# Connecto-mcu.net
KiCad netlist of a schematic drawn in Altium Designer
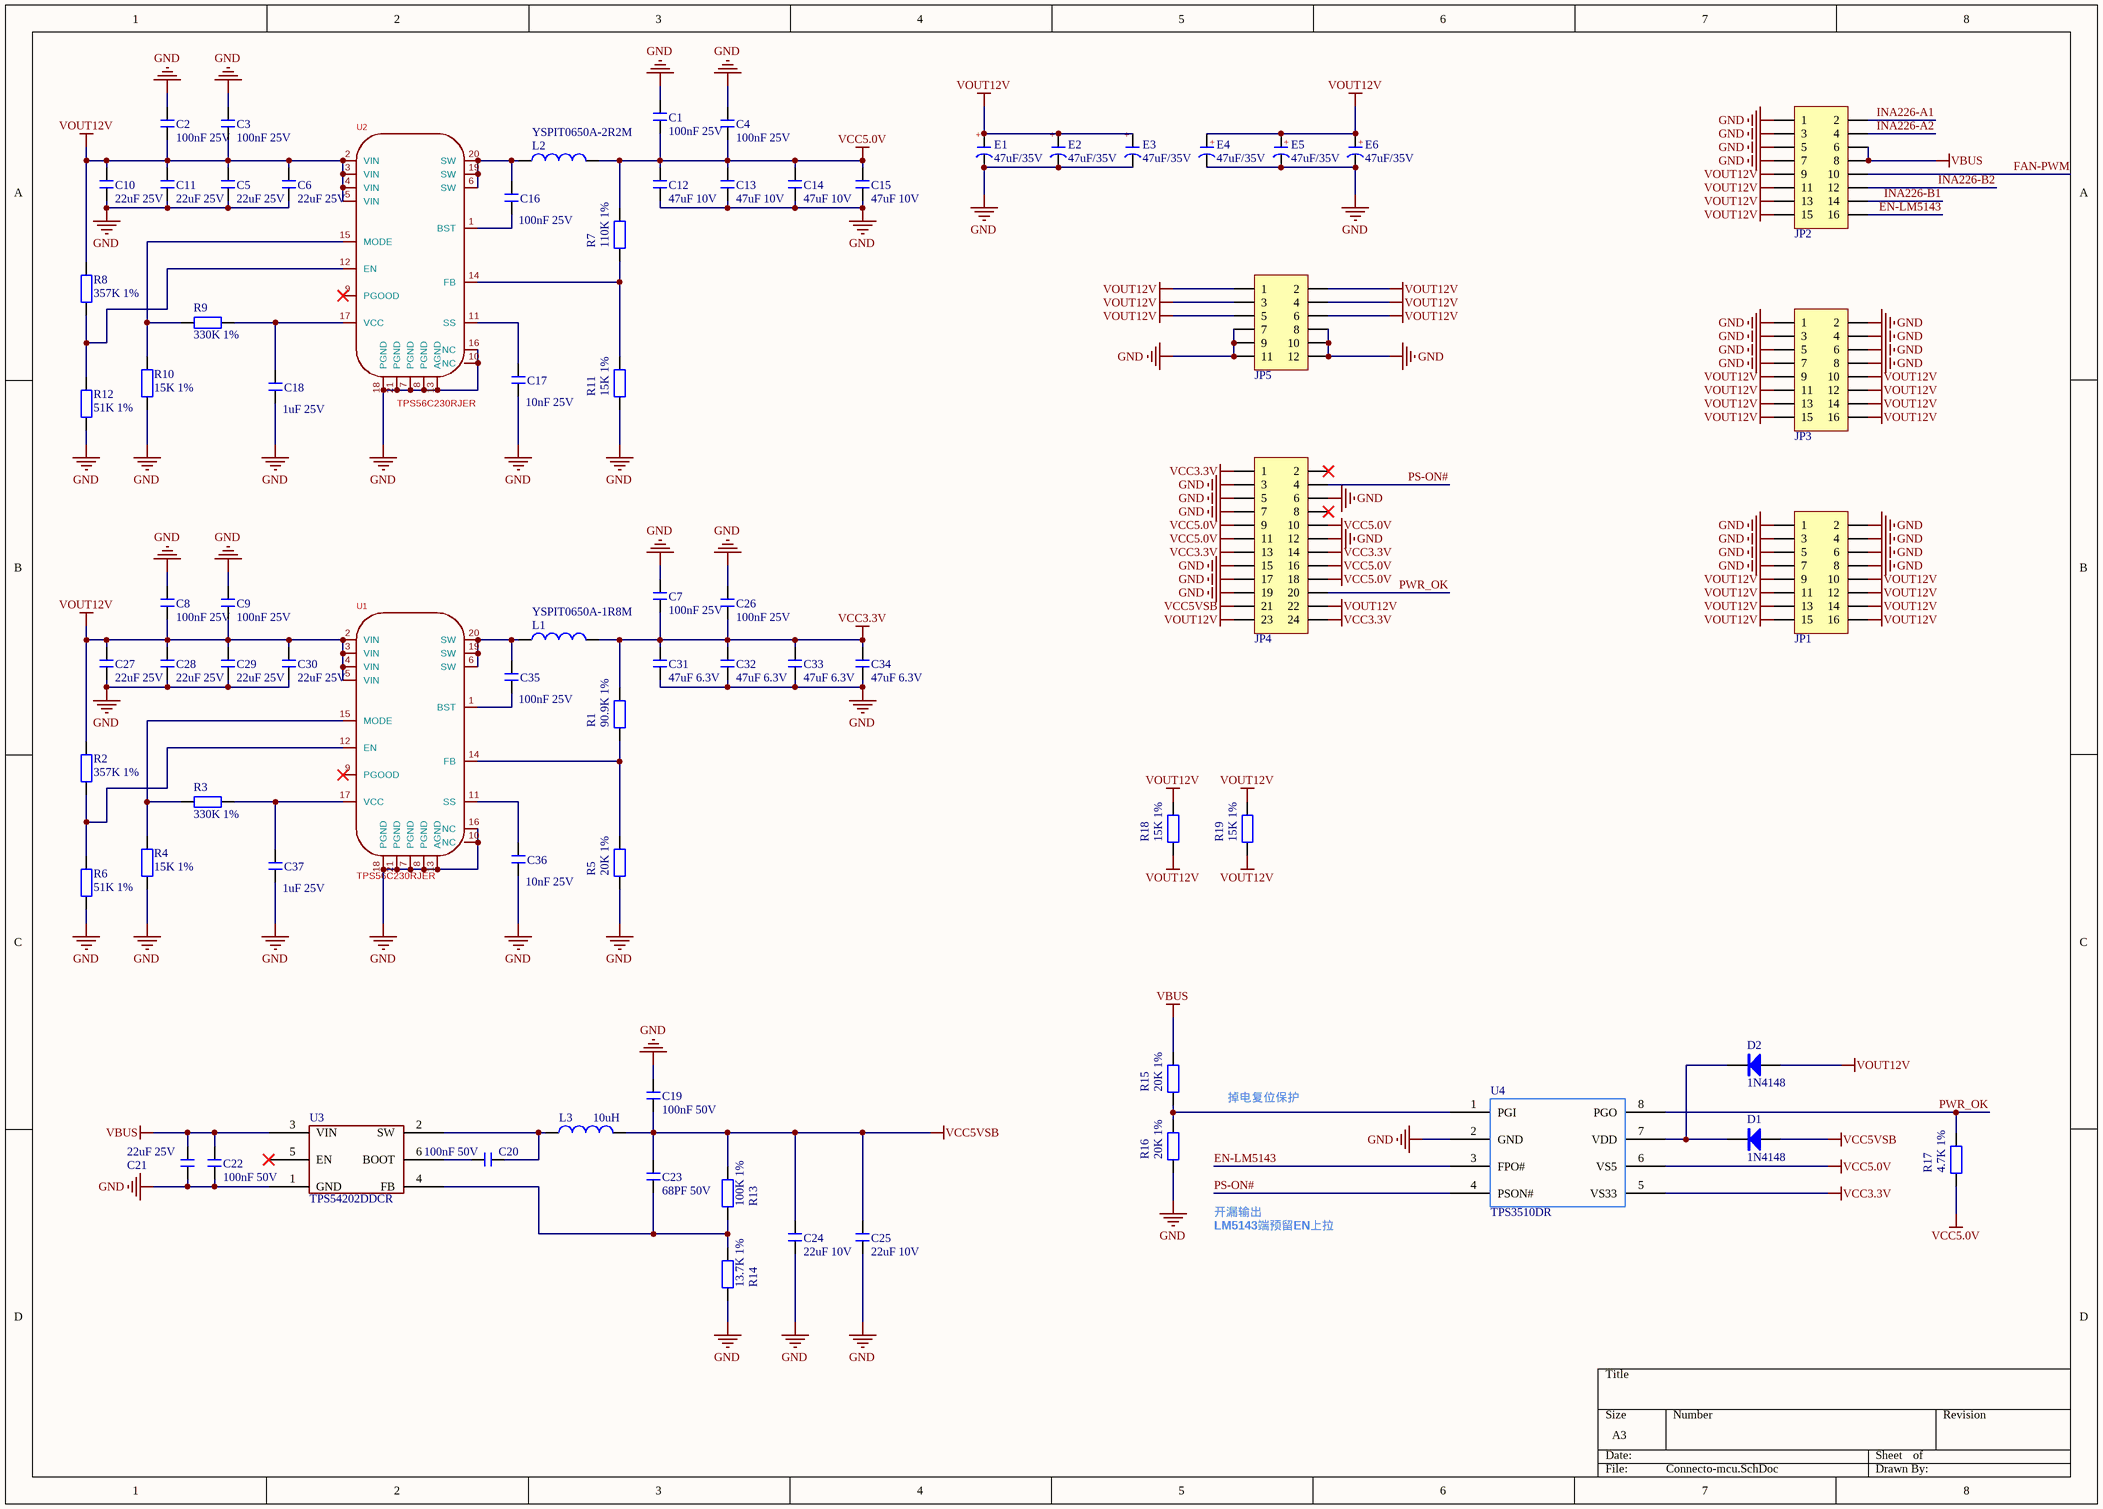
[diagram p0: Connecto-mcu.SchDoc]

(export (version "E")
  (design (tool "Eeschema 10.0.6"))
  (components
    (comp (ref "C1")
      (value "100nF 25V")
      (footprint "C0805_L")
      (description "无极性贴片电容")
      (fields (field (name "版权归属") "源创客"))
      (libsource (lib "Capacitor") (part "C"))
    )
    (comp (ref "C2")
      (value "100nF 25V")
      (footprint "C0402_L")
      (description "无极性贴片电容")
      (fields (field (name "版权归属") "源创客"))
      (libsource (lib "Capacitor") (part "C"))
    )
    (comp (ref "C3")
      (value "100nF 25V")
      (footprint "C0402_L")
      (description "无极性贴片电容")
      (fields (field (name "版权归属") "源创客"))
      (libsource (lib "Capacitor") (part "C"))
    )
    (comp (ref "C4")
      (value "100nF 25V")
      (footprint "C0805_L")
      (description "无极性贴片电容")
      (fields (field (name "版权归属") "源创客"))
      (libsource (lib "Capacitor") (part "C"))
    )
    (comp (ref "C5")
      (value "22uF 25V")
      (footprint "C0805_L")
      (description "无极性贴片电容")
      (fields (field (name "版权归属") "源创客"))
      (libsource (lib "Capacitor") (part "C"))
    )
    (comp (ref "C6")
      (value "22uF 25V")
      (footprint "C0805_L")
      (description "无极性贴片电容")
      (fields (field (name "版权归属") "源创客"))
      (libsource (lib "Capacitor") (part "C"))
    )
    (comp (ref "C7")
      (value "100nF 25V")
      (footprint "C0805_L")
      (description "无极性贴片电容")
      (fields (field (name "版权归属") "源创客"))
      (libsource (lib "Capacitor") (part "C"))
    )
    (comp (ref "C8")
      (value "100nF 25V")
      (footprint "C0402_L")
      (description "无极性贴片电容")
      (fields (field (name "版权归属") "源创客"))
      (libsource (lib "Capacitor") (part "C"))
    )
    (comp (ref "C9")
      (value "100nF 25V")
      (footprint "C0402_L")
      (description "无极性贴片电容")
      (fields (field (name "版权归属") "源创客"))
      (libsource (lib "Capacitor") (part "C"))
    )
    (comp (ref "C10")
      (value "22uF 25V")
      (footprint "C0805_L")
      (description "无极性贴片电容")
      (fields (field (name "版权归属") "源创客"))
      (libsource (lib "Capacitor") (part "C"))
    )
    (comp (ref "C11")
      (value "22uF 25V")
      (footprint "C0805_L")
      (description "无极性贴片电容")
      (fields (field (name "版权归属") "源创客"))
      (libsource (lib "Capacitor") (part "C"))
    )
    (comp (ref "C12")
      (value "47uF 10V")
      (footprint "C0805_L")
      (description "无极性贴片电容")
      (fields (field (name "版权归属") "源创客"))
      (libsource (lib "Capacitor") (part "C"))
    )
    (comp (ref "C13")
      (value "47uF 10V")
      (footprint "C0805_L")
      (description "无极性贴片电容")
      (fields (field (name "版权归属") "源创客"))
      (libsource (lib "Capacitor") (part "C"))
    )
    (comp (ref "C14")
      (value "47uF 10V")
      (footprint "C0805_L")
      (description "无极性贴片电容")
      (fields (field (name "版权归属") "源创客"))
      (libsource (lib "Capacitor") (part "C"))
    )
    (comp (ref "C15")
      (value "47uF 10V")
      (footprint "C0805_L")
      (description "无极性贴片电容")
      (fields (field (name "版权归属") "源创客"))
      (libsource (lib "Capacitor") (part "C"))
    )
    (comp (ref "C16")
      (value "100nF 25V")
      (footprint "C0402_L")
      (description "无极性贴片电容")
      (fields (field (name "版权归属") "源创客"))
      (libsource (lib "Capacitor") (part "C"))
    )
    (comp (ref "C17")
      (value "10nF 25V")
      (footprint "C0402_L")
      (description "无极性贴片电容")
      (fields (field (name "版权归属") "源创客"))
      (libsource (lib "Capacitor") (part "C"))
    )
    (comp (ref "C18")
      (value "1uF 25V")
      (footprint "C0402_L")
      (description "无极性贴片电容")
      (fields (field (name "版权归属") "源创客"))
      (libsource (lib "Capacitor") (part "C"))
    )
    (comp (ref "C19")
      (value "100nF 50V")
      (footprint "C0402_L")
      (description "无极性贴片电容")
      (fields (field (name "版权归属") "源创客"))
      (libsource (lib "Capacitor") (part "C"))
    )
    (comp (ref "C20")
      (value "100nF 50V")
      (footprint "C0402_L")
      (description "无极性贴片电容")
      (fields (field (name "版权归属") "源创客"))
      (libsource (lib "Capacitor") (part "C"))
    )
    (comp (ref "C21")
      (value "22uF 25V")
      (footprint "C0805_L")
      (description "无极性贴片电容")
      (fields (field (name "版权归属") "源创客"))
      (libsource (lib "Capacitor") (part "C"))
    )
    (comp (ref "C22")
      (value "100nF 50V")
      (footprint "C0402_L")
      (description "无极性贴片电容")
      (fields (field (name "版权归属") "源创客"))
      (libsource (lib "Capacitor") (part "C"))
    )
    (comp (ref "C23")
      (value "68PF 50V")
      (footprint "C0402_L")
      (description "无极性贴片电容")
      (fields (field (name "版权归属") "源创客"))
      (libsource (lib "Capacitor") (part "C"))
    )
    (comp (ref "C24")
      (value "22uF 10V")
      (footprint "C0805_L")
      (description "无极性贴片电容")
      (fields (field (name "版权归属") "源创客"))
      (libsource (lib "Capacitor") (part "C"))
    )
    (comp (ref "C25")
      (value "22uF 10V")
      (footprint "C0805_L")
      (description "无极性贴片电容")
      (fields (field (name "版权归属") "源创客"))
      (libsource (lib "Capacitor") (part "C"))
    )
    (comp (ref "C26")
      (value "100nF 25V")
      (footprint "C0805_L")
      (description "无极性贴片电容")
      (fields (field (name "版权归属") "源创客"))
      (libsource (lib "Capacitor") (part "C"))
    )
    (comp (ref "C27")
      (value "22uF 25V")
      (footprint "C0805_L")
      (description "无极性贴片电容")
      (fields (field (name "版权归属") "源创客"))
      (libsource (lib "Capacitor") (part "C"))
    )
    (comp (ref "C28")
      (value "22uF 25V")
      (footprint "C0805_L")
      (description "无极性贴片电容")
      (fields (field (name "版权归属") "源创客"))
      (libsource (lib "Capacitor") (part "C"))
    )
    (comp (ref "C29")
      (value "22uF 25V")
      (footprint "C0805_L")
      (description "无极性贴片电容")
      (fields (field (name "版权归属") "源创客"))
      (libsource (lib "Capacitor") (part "C"))
    )
    (comp (ref "C30")
      (value "22uF 25V")
      (footprint "C0805_L")
      (description "无极性贴片电容")
      (fields (field (name "版权归属") "源创客"))
      (libsource (lib "Capacitor") (part "C"))
    )
    (comp (ref "C31")
      (value "47uF 6.3V")
      (footprint "C0805_L")
      (description "无极性贴片电容")
      (fields (field (name "版权归属") "源创客"))
      (libsource (lib "Capacitor") (part "C"))
    )
    (comp (ref "C32")
      (value "47uF 6.3V")
      (footprint "C0805_L")
      (description "无极性贴片电容")
      (fields (field (name "版权归属") "源创客"))
      (libsource (lib "Capacitor") (part "C"))
    )
    (comp (ref "C33")
      (value "47uF 6.3V")
      (footprint "C0805_L")
      (description "无极性贴片电容")
      (fields (field (name "版权归属") "源创客"))
      (libsource (lib "Capacitor") (part "C"))
    )
    (comp (ref "C34")
      (value "47uF 6.3V")
      (footprint "C0805_L")
      (description "无极性贴片电容")
      (fields (field (name "版权归属") "源创客"))
      (libsource (lib "Capacitor") (part "C"))
    )
    (comp (ref "C35")
      (value "100nF 25V")
      (footprint "C0402_L")
      (description "无极性贴片电容")
      (fields (field (name "版权归属") "源创客"))
      (libsource (lib "Capacitor") (part "C"))
    )
    (comp (ref "C36")
      (value "10nF 25V")
      (footprint "C0402_L")
      (description "无极性贴片电容")
      (fields (field (name "版权归属") "源创客"))
      (libsource (lib "Capacitor") (part "C"))
    )
    (comp (ref "C37")
      (value "1uF 25V")
      (footprint "C0402_L")
      (description "无极性贴片电容")
      (fields (field (name "版权归属") "源创客"))
      (libsource (lib "Capacitor") (part "C"))
    )
    (comp (ref "D1")
      (value "1N4148")
      (footprint "SOD-523_L1.2-W0.8-LS1.6-FD")
      (description "整流二极管")
      (fields (field (name "版权归属") "源创客"))
      (libsource (lib "Diode") (part "1N4007"))
    )
    (comp (ref "D2")
      (value "1N4148")
      (footprint "SOD-523_L1.2-W0.8-LS1.6-FD")
      (description "整流二极管")
      (fields (field (name "版权归属") "源创客"))
      (libsource (lib "Diode") (part "1N4007"))
    )
    (comp (ref "E1")
      (value "47uF/35V")
      (footprint "CT 6*6 - V -A")
      (description "直插电解电容")
      (fields (field (name "版权归属") "源创客"))
      (libsource (lib "Capacitor") (part "C-CAP"))
    )
    (comp (ref "E2")
      (value "47uF/35V")
      (footprint "CT 6*6 - V -A")
      (description "直插电解电容")
      (fields (field (name "版权归属") "源创客"))
      (libsource (lib "Capacitor") (part "C-CAP"))
    )
    (comp (ref "E3")
      (value "47uF/35V")
      (footprint "CT 6*6 - V -A")
      (description "直插电解电容")
      (fields (field (name "版权归属") "源创客"))
      (libsource (lib "Capacitor") (part "C-CAP"))
    )
    (comp (ref "E4")
      (value "47uF/35V")
      (footprint "CT 6*6 - V -A")
      (description "直插电解电容")
      (fields (field (name "版权归属") "源创客"))
      (libsource (lib "") (part "C-CAP_1"))
    )
    (comp (ref "E5")
      (value "47uF/35V")
      (footprint "CT 6*6 - V -A")
      (description "直插电解电容")
      (fields (field (name "版权归属") "源创客"))
      (libsource (lib "") (part "C-CAP_1"))
    )
    (comp (ref "E6")
      (value "47uF/35V")
      (footprint "CT 6*6 - V -A")
      (description "直插电解电容")
      (fields (field (name "版权归属") "源创客"))
      (libsource (lib "") (part "C-CAP_1"))
    )
    (comp (ref "JP1")
      (value "Header 8X2")
      (footprint "HDR2.54-LI-2x8P")
      (description "8*2P接插件")
      (fields (field (name "版权归属") "源创客"))
      (libsource (lib "Connector-PinHeader") (part "Header 8X2"))
    )
    (comp (ref "JP2")
      (value "Header 8X2")
      (footprint "HDR2.54-LI-2x8P")
      (description "8*2P接插件")
      (fields (field (name "版权归属") "源创客"))
      (libsource (lib "Connector-PinHeader") (part "Header 8X2"))
    )
    (comp (ref "JP3")
      (value "Header 8X2")
      (footprint "HDR2.54-LI-2x8P")
      (description "8*2P接插件")
      (fields (field (name "版权归属") "源创客"))
      (libsource (lib "Connector-PinHeader") (part "Header 8X2"))
    )
    (comp (ref "JP4")
      (value "Header 2X11")
      (footprint "MX3.0 2X12 Pin 卧贴")
      (description "12*2P接插件")
      (fields (field (name "版权归属") "源创客"))
      (libsource (lib "Connector-PinHeader") (part "Header 12X2"))
    )
    (comp (ref "JP5")
      (value "Header 6X2")
      (footprint "MX3.0 2X6 Pin 卧贴")
      (description "6*2P接插件")
      (fields (field (name "版权归属") "源创客"))
      (libsource (lib "Connector-PinHeader") (part "Header  6X2"))
    )
    (comp (ref "L1")
      (value "YSPIT0650A-1R8M")
      (footprint "NR6045")
      (description "小功率贴片电感")
      (fields (field (name "版权归属") "源创客"))
      (libsource (lib "Inductor") (part "L"))
    )
    (comp (ref "L2")
      (value "YSPIT0650A-2R2M")
      (footprint "NR6045")
      (description "小功率贴片电感")
      (fields (field (name "版权归属") "源创客"))
      (libsource (lib "Inductor") (part "L"))
    )
    (comp (ref "L3")
      (value "10uH")
      (footprint "SMMS0420")
      (description "小功率贴片电感")
      (fields (field (name "版权归属") "源创客"))
      (libsource (lib "Inductor") (part "L"))
    )
    (comp (ref "R1")
      (value "90.9K 1%")
      (footprint "R0402_L")
      (description "贴片电阻")
      (fields (field (name "版权归属") "源创客"))
      (libsource (lib "Resistor") (part "R"))
    )
    (comp (ref "R2")
      (value "357K 1%")
      (footprint "R0402_L")
      (description "贴片电阻")
      (fields (field (name "版权归属") "源创客"))
      (libsource (lib "Resistor") (part "R"))
    )
    (comp (ref "R3")
      (value "330K 1%")
      (footprint "R0402_L")
      (description "贴片电阻")
      (fields (field (name "版权归属") "源创客"))
      (libsource (lib "Resistor") (part "R"))
    )
    (comp (ref "R4")
      (value "15K 1%")
      (footprint "R0402_L")
      (description "贴片电阻")
      (fields (field (name "版权归属") "源创客"))
      (libsource (lib "Resistor") (part "R"))
    )
    (comp (ref "R5")
      (value "20K 1%")
      (footprint "R0402_L")
      (description "贴片电阻")
      (fields (field (name "版权归属") "源创客"))
      (libsource (lib "Resistor") (part "R"))
    )
    (comp (ref "R6")
      (value "51K 1%")
      (footprint "R0402_L")
      (description "贴片电阻")
      (fields (field (name "版权归属") "源创客"))
      (libsource (lib "Resistor") (part "R"))
    )
    (comp (ref "R7")
      (value "110K 1%")
      (footprint "R0402_L")
      (description "贴片电阻")
      (fields (field (name "版权归属") "源创客"))
      (libsource (lib "Resistor") (part "R"))
    )
    (comp (ref "R8")
      (value "357K 1%")
      (footprint "R0402_L")
      (description "贴片电阻")
      (fields (field (name "版权归属") "源创客"))
      (libsource (lib "Resistor") (part "R"))
    )
    (comp (ref "R9")
      (value "330K 1%")
      (footprint "R0402_L")
      (description "贴片电阻")
      (fields (field (name "版权归属") "源创客"))
      (libsource (lib "Resistor") (part "R"))
    )
    (comp (ref "R10")
      (value "15K 1%")
      (footprint "R0402_L")
      (description "贴片电阻")
      (fields (field (name "版权归属") "源创客"))
      (libsource (lib "Resistor") (part "R"))
    )
    (comp (ref "R11")
      (value "15K 1%")
      (footprint "R0402_L")
      (description "贴片电阻")
      (fields (field (name "版权归属") "源创客"))
      (libsource (lib "Resistor") (part "R"))
    )
    (comp (ref "R12")
      (value "51K 1%")
      (footprint "R0402_L")
      (description "贴片电阻")
      (fields (field (name "版权归属") "源创客"))
      (libsource (lib "Resistor") (part "R"))
    )
    (comp (ref "R13")
      (value "100K 1%")
      (footprint "R0402_L")
      (description "贴片电阻")
      (fields (field (name "版权归属") "源创客"))
      (libsource (lib "Resistor") (part "R"))
    )
    (comp (ref "R14")
      (value "13.7K 1%")
      (footprint "R0402_L")
      (description "贴片电阻")
      (fields (field (name "版权归属") "源创客"))
      (libsource (lib "Resistor") (part "R"))
    )
    (comp (ref "R15")
      (value "20K 1%")
      (footprint "R0402_L")
      (description "贴片电阻")
      (fields (field (name "版权归属") "源创客"))
      (libsource (lib "Resistor") (part "R"))
    )
    (comp (ref "R16")
      (value "20K 1%")
      (footprint "R0402_L")
      (description "贴片电阻")
      (fields (field (name "版权归属") "源创客"))
      (libsource (lib "Resistor") (part "R"))
    )
    (comp (ref "R17")
      (value "4.7K 1%")
      (footprint "R0402_L")
      (description "贴片电阻")
      (fields (field (name "版权归属") "源创客"))
      (libsource (lib "Resistor") (part "R"))
    )
    (comp (ref "R18")
      (value "15K 1%")
      (footprint "内嵌载流铜条 2x2x66.5mm")
      (description "贴片电阻")
      (fields (field (name "版权归属") "源创客"))
      (libsource (lib "Resistor") (part "R"))
    )
    (comp (ref "R19")
      (value "15K 1%")
      (footprint "内嵌载流铜条 2x2x66.5mm")
      (description "贴片电阻")
      (fields (field (name "版权归属") "源创客"))
      (libsource (lib "Resistor") (part "R"))
    )
    (comp (ref "U1")
      (value "TPS56C230RJER")
      (footprint "VQFN-20_L3.0-W3.0-P0.45-TL-EP_TI_RJE")
      (description "功能类型:降压型;输出类型:可调;输入电压:4.5V~18V;输出电压:600mV~5.5V;输出电流(最大值):12A;")
      (fields (field (name "MANUFACTURER") "TI(德州仪器)"))
      (libsource (lib "DCDC Convert") (part "TPS56C230RJER"))
    )
    (comp (ref "U2")
      (value "TPS56C230RJER")
      (footprint "VQFN-20_L3.0-W3.0-P0.45-TL-EP_TI_RJE")
      (description "功能类型:降压型;输出类型:可调;输入电压:4.5V~18V;输出电压:600mV~5.5V;输出电流(最大值):12A;")
      (fields (field (name "MANUFACTURER") "TI(德州仪器)"))
      (libsource (lib "DCDC Convert") (part "TPS56C230RJER"))
    )
    (comp (ref "U3")
      (value "TPS54202DDCR")
      (footprint "SOT23-6L")
      (description "DCDC Convert")
      (libsource (lib "DCDC Convert") (part "TPS54202DDCR"))
    )
    (comp (ref "U4")
      (value "TPS3510DR")
      (footprint "SOP8_N")
      (description "TPS3510 适用于开关模式电源的 3 通道监控器")
      (libsource (lib "监控和复位芯片") (part "TPS3510DR"))
    )
  )
  (nets
    (net (code "1") (name "/EN-LM5143") (class "Default")
      (node (ref "JP2") (pin "16") (pinfunction "16_16") (pintype "passive"))
      (node (ref "U4") (pin "3") (pinfunction "FPO#_3") (pintype "passive"))
    )
    (net (code "2") (name "/FAN-PWM") (class "Default")
      (node (ref "JP2") (pin "10") (pinfunction "10_10") (pintype "passive"))
    )
    (net (code "3") (name "/INA226-A1") (class "Default")
      (node (ref "JP2") (pin "2") (pinfunction "2_2") (pintype "passive"))
    )
    (net (code "4") (name "/INA226-A2") (class "Default")
      (node (ref "JP2") (pin "4") (pinfunction "4_4") (pintype "passive"))
    )
    (net (code "5") (name "/INA226-B1") (class "Default")
      (node (ref "JP2") (pin "14") (pinfunction "14_14") (pintype "passive"))
    )
    (net (code "6") (name "/INA226-B2") (class "Default")
      (node (ref "JP2") (pin "12") (pinfunction "12_12") (pintype "passive"))
    )
    (net (code "7") (name "/PS-ON#") (class "Default")
      (node (ref "JP4") (pin "4") (pinfunction "4_4") (pintype "passive"))
      (node (ref "U4") (pin "4") (pinfunction "PSON#_4") (pintype "passive"))
    )
    (net (code "8") (name "/PWR_OK") (class "Default")
      (node (ref "JP4") (pin "20") (pinfunction "20_20") (pintype "passive"))
      (node (ref "R17") (pin "1") (pinfunction "1_1") (pintype "passive"))
      (node (ref "U4") (pin "8") (pinfunction "PGO_8") (pintype "passive"))
    )
    (net (code "9") (name "GND") (class "Default")
      (node (ref "C1") (pin "2") (pinfunction "2_2") (pintype "passive"))
      (node (ref "C10") (pin "1") (pinfunction "1_1") (pintype "passive"))
      (node (ref "C11") (pin "1") (pinfunction "1_1") (pintype "passive"))
      (node (ref "C12") (pin "1") (pinfunction "1_1") (pintype "passive"))
      (node (ref "C13") (pin "1") (pinfunction "1_1") (pintype "passive"))
      (node (ref "C14") (pin "1") (pinfunction "1_1") (pintype "passive"))
      (node (ref "C15") (pin "1") (pinfunction "1_1") (pintype "passive"))
      (node (ref "C17") (pin "1") (pinfunction "1_1") (pintype "passive"))
      (node (ref "C18") (pin "1") (pinfunction "1_1") (pintype "passive"))
      (node (ref "C19") (pin "2") (pinfunction "2_2") (pintype "passive"))
      (node (ref "C2") (pin "2") (pinfunction "2_2") (pintype "passive"))
      (node (ref "C21") (pin "1") (pinfunction "1_1") (pintype "passive"))
      (node (ref "C22") (pin "1") (pinfunction "1_1") (pintype "passive"))
      (node (ref "C24") (pin "2") (pinfunction "2_2") (pintype "passive"))
      (node (ref "C25") (pin "2") (pinfunction "2_2") (pintype "passive"))
      (node (ref "C26") (pin "2") (pinfunction "2_2") (pintype "passive"))
      (node (ref "C27") (pin "1") (pinfunction "1_1") (pintype "passive"))
      (node (ref "C28") (pin "1") (pinfunction "1_1") (pintype "passive"))
      (node (ref "C29") (pin "1") (pinfunction "1_1") (pintype "passive"))
      (node (ref "C3") (pin "2") (pinfunction "2_2") (pintype "passive"))
      (node (ref "C30") (pin "1") (pinfunction "1_1") (pintype "passive"))
      (node (ref "C31") (pin "1") (pinfunction "1_1") (pintype "passive"))
      (node (ref "C32") (pin "1") (pinfunction "1_1") (pintype "passive"))
      (node (ref "C33") (pin "1") (pinfunction "1_1") (pintype "passive"))
      (node (ref "C34") (pin "1") (pinfunction "1_1") (pintype "passive"))
      (node (ref "C36") (pin "1") (pinfunction "1_1") (pintype "passive"))
      (node (ref "C37") (pin "1") (pinfunction "1_1") (pintype "passive"))
      (node (ref "C4") (pin "2") (pinfunction "2_2") (pintype "passive"))
      (node (ref "C5") (pin "1") (pinfunction "1_1") (pintype "passive"))
      (node (ref "C6") (pin "1") (pinfunction "1_1") (pintype "passive"))
      (node (ref "C7") (pin "2") (pinfunction "2_2") (pintype "passive"))
      (node (ref "C8") (pin "2") (pinfunction "2_2") (pintype "passive"))
      (node (ref "C9") (pin "2") (pinfunction "2_2") (pintype "passive"))
      (node (ref "E1") (pin "2") (pinfunction "K_2") (pintype "passive"))
      (node (ref "E2") (pin "2") (pinfunction "K_2") (pintype "passive"))
      (node (ref "E3") (pin "2") (pinfunction "K_2") (pintype "passive"))
      (node (ref "E4") (pin "2") (pinfunction "K_2") (pintype "passive"))
      (node (ref "E5") (pin "2") (pinfunction "K_2") (pintype "passive"))
      (node (ref "E6") (pin "2") (pinfunction "K_2") (pintype "passive"))
      (node (ref "JP1") (pin "1") (pinfunction "1_1") (pintype "passive"))
      (node (ref "JP1") (pin "2") (pinfunction "2_2") (pintype "passive"))
      (node (ref "JP1") (pin "3") (pinfunction "3_3") (pintype "passive"))
      (node (ref "JP1") (pin "4") (pinfunction "4_4") (pintype "passive"))
      (node (ref "JP1") (pin "5") (pinfunction "5_5") (pintype "passive"))
      (node (ref "JP1") (pin "6") (pinfunction "6_6") (pintype "passive"))
      (node (ref "JP1") (pin "7") (pinfunction "7_7") (pintype "passive"))
      (node (ref "JP1") (pin "8") (pinfunction "8_8") (pintype "passive"))
      (node (ref "JP2") (pin "1") (pinfunction "1_1") (pintype "passive"))
      (node (ref "JP2") (pin "3") (pinfunction "3_3") (pintype "passive"))
      (node (ref "JP2") (pin "5") (pinfunction "5_5") (pintype "passive"))
      (node (ref "JP2") (pin "7") (pinfunction "7_7") (pintype "passive"))
      (node (ref "JP3") (pin "1") (pinfunction "1_1") (pintype "passive"))
      (node (ref "JP3") (pin "2") (pinfunction "2_2") (pintype "passive"))
      (node (ref "JP3") (pin "3") (pinfunction "3_3") (pintype "passive"))
      (node (ref "JP3") (pin "4") (pinfunction "4_4") (pintype "passive"))
      (node (ref "JP3") (pin "5") (pinfunction "5_5") (pintype "passive"))
      (node (ref "JP3") (pin "6") (pinfunction "6_6") (pintype "passive"))
      (node (ref "JP3") (pin "7") (pinfunction "7_7") (pintype "passive"))
      (node (ref "JP3") (pin "8") (pinfunction "8_8") (pintype "passive"))
      (node (ref "JP4") (pin "12") (pinfunction "12_12") (pintype "passive"))
      (node (ref "JP4") (pin "15") (pinfunction "15_15") (pintype "passive"))
      (node (ref "JP4") (pin "17") (pinfunction "17_17") (pintype "passive"))
      (node (ref "JP4") (pin "19") (pinfunction "19_19") (pintype "passive"))
      (node (ref "JP4") (pin "3") (pinfunction "3_3") (pintype "passive"))
      (node (ref "JP4") (pin "5") (pinfunction "5_5") (pintype "passive"))
      (node (ref "JP4") (pin "6") (pinfunction "6_6") (pintype "passive"))
      (node (ref "JP4") (pin "7") (pinfunction "7_7") (pintype "passive"))
      (node (ref "JP5") (pin "10") (pinfunction "10_10") (pintype "passive"))
      (node (ref "JP5") (pin "11") (pinfunction "11_11") (pintype "passive"))
      (node (ref "JP5") (pin "12") (pinfunction "12_12") (pintype "passive"))
      (node (ref "JP5") (pin "7") (pinfunction "7_7") (pintype "passive"))
      (node (ref "JP5") (pin "8") (pinfunction "8_8") (pintype "passive"))
      (node (ref "JP5") (pin "9") (pinfunction "9_9") (pintype "passive"))
      (node (ref "R10") (pin "1") (pinfunction "1_1") (pintype "passive"))
      (node (ref "R11") (pin "2") (pinfunction "2_2") (pintype "passive"))
      (node (ref "R12") (pin "1") (pinfunction "1_1") (pintype "passive"))
      (node (ref "R14") (pin "2") (pinfunction "2_2") (pintype "passive"))
      (node (ref "R16") (pin "2") (pinfunction "2_2") (pintype "passive"))
      (node (ref "R4") (pin "1") (pinfunction "1_1") (pintype "passive"))
      (node (ref "R5") (pin "2") (pinfunction "2_2") (pintype "passive"))
      (node (ref "R6") (pin "1") (pinfunction "1_1") (pintype "passive"))
      (node (ref "U1") (pin "10") (pinfunction "NC_10") (pintype "passive"))
      (node (ref "U1") (pin "13") (pinfunction "AGND_13") (pintype "passive"))
      (node (ref "U1") (pin "16") (pinfunction "NC_16") (pintype "passive"))
      (node (ref "U1") (pin "18") (pinfunction "PGND_18") (pintype "passive"))
      (node (ref "U1") (pin "21") (pinfunction "PGND_21") (pintype "passive"))
      (node (ref "U1") (pin "7") (pinfunction "PGND_7") (pintype "passive"))
      (node (ref "U1") (pin "8") (pinfunction "PGND_8") (pintype "passive"))
      (node (ref "U2") (pin "10") (pinfunction "NC_10") (pintype "passive"))
      (node (ref "U2") (pin "13") (pinfunction "AGND_13") (pintype "passive"))
      (node (ref "U2") (pin "16") (pinfunction "NC_16") (pintype "passive"))
      (node (ref "U2") (pin "18") (pinfunction "PGND_18") (pintype "passive"))
      (node (ref "U2") (pin "21") (pinfunction "PGND_21") (pintype "passive"))
      (node (ref "U2") (pin "7") (pinfunction "PGND_7") (pintype "passive"))
      (node (ref "U2") (pin "8") (pinfunction "PGND_8") (pintype "passive"))
      (node (ref "U3") (pin "1") (pinfunction "GND_1") (pintype "passive"))
      (node (ref "U4") (pin "2") (pinfunction "GND_2") (pintype "passive"))
    )
    (net (code "10") (name "Net-(C16-Pad2)") (class "Default")
      (node (ref "C16") (pin "2") (pinfunction "2_2") (pintype "passive"))
      (node (ref "L2") (pin "1") (pinfunction "1_1") (pintype "passive"))
      (node (ref "U2") (pin "19") (pinfunction "SW_19") (pintype "passive"))
      (node (ref "U2") (pin "20") (pinfunction "SW_20") (pintype "passive"))
      (node (ref "U2") (pin "6") (pinfunction "SW_6") (pintype "passive"))
    )
    (net (code "11") (name "Net-(C35-Pad2)") (class "Default")
      (node (ref "C35") (pin "2") (pinfunction "2_2") (pintype "passive"))
      (node (ref "L1") (pin "1") (pinfunction "1_1") (pintype "passive"))
      (node (ref "U1") (pin "19") (pinfunction "SW_19") (pintype "passive"))
      (node (ref "U1") (pin "20") (pinfunction "SW_20") (pintype "passive"))
      (node (ref "U1") (pin "6") (pinfunction "SW_6") (pintype "passive"))
    )
    (net (code "12") (name "Net-(D1-K)") (class "Default")
      (node (ref "D1") (pin "2") (pinfunction "K_2") (pintype "passive"))
      (node (ref "D2") (pin "2") (pinfunction "K_2") (pintype "passive"))
      (node (ref "U4") (pin "7") (pinfunction "VDD_7") (pintype "passive"))
    )
    (net (code "13") (name "Net-(U1-BST)") (class "Default")
      (node (ref "C35") (pin "1") (pinfunction "1_1") (pintype "passive"))
      (node (ref "U1") (pin "1") (pinfunction "BST_1") (pintype "passive"))
    )
    (net (code "14") (name "Net-(U1-EN)") (class "Default")
      (node (ref "R2") (pin "1") (pinfunction "1_1") (pintype "passive"))
      (node (ref "R6") (pin "2") (pinfunction "2_2") (pintype "passive"))
      (node (ref "U1") (pin "12") (pinfunction "EN_12") (pintype "passive"))
    )
    (net (code "15") (name "Net-(U1-FB)") (class "Default")
      (node (ref "R1") (pin "2") (pinfunction "2_2") (pintype "passive"))
      (node (ref "R5") (pin "1") (pinfunction "1_1") (pintype "passive"))
      (node (ref "U1") (pin "14") (pinfunction "FB_14") (pintype "passive"))
    )
    (net (code "16") (name "Net-(U1-MODE)") (class "Default")
      (node (ref "R3") (pin "2") (pinfunction "2_2") (pintype "passive"))
      (node (ref "R4") (pin "2") (pinfunction "2_2") (pintype "passive"))
      (node (ref "U1") (pin "15") (pinfunction "MODE_15") (pintype "passive"))
    )
    (net (code "17") (name "Net-(U1-SS)") (class "Default")
      (node (ref "C36") (pin "2") (pinfunction "2_2") (pintype "passive"))
      (node (ref "U1") (pin "11") (pinfunction "SS_11") (pintype "passive"))
    )
    (net (code "18") (name "Net-(U1-VCC)") (class "Default")
      (node (ref "C37") (pin "2") (pinfunction "2_2") (pintype "passive"))
      (node (ref "R3") (pin "1") (pinfunction "1_1") (pintype "passive"))
      (node (ref "U1") (pin "17") (pinfunction "VCC_17") (pintype "passive"))
    )
    (net (code "19") (name "Net-(U2-BST)") (class "Default")
      (node (ref "C16") (pin "1") (pinfunction "1_1") (pintype "passive"))
      (node (ref "U2") (pin "1") (pinfunction "BST_1") (pintype "passive"))
    )
    (net (code "20") (name "Net-(U2-EN)") (class "Default")
      (node (ref "R12") (pin "2") (pinfunction "2_2") (pintype "passive"))
      (node (ref "R8") (pin "1") (pinfunction "1_1") (pintype "passive"))
      (node (ref "U2") (pin "12") (pinfunction "EN_12") (pintype "passive"))
    )
    (net (code "21") (name "Net-(U2-FB)") (class "Default")
      (node (ref "R11") (pin "1") (pinfunction "1_1") (pintype "passive"))
      (node (ref "R7") (pin "2") (pinfunction "2_2") (pintype "passive"))
      (node (ref "U2") (pin "14") (pinfunction "FB_14") (pintype "passive"))
    )
    (net (code "22") (name "Net-(U2-MODE)") (class "Default")
      (node (ref "R10") (pin "2") (pinfunction "2_2") (pintype "passive"))
      (node (ref "R9") (pin "2") (pinfunction "2_2") (pintype "passive"))
      (node (ref "U2") (pin "15") (pinfunction "MODE_15") (pintype "passive"))
    )
    (net (code "23") (name "Net-(U2-SS)") (class "Default")
      (node (ref "C17") (pin "2") (pinfunction "2_2") (pintype "passive"))
      (node (ref "U2") (pin "11") (pinfunction "SS_11") (pintype "passive"))
    )
    (net (code "24") (name "Net-(U2-VCC)") (class "Default")
      (node (ref "C18") (pin "2") (pinfunction "2_2") (pintype "passive"))
      (node (ref "R9") (pin "1") (pinfunction "1_1") (pintype "passive"))
      (node (ref "U2") (pin "17") (pinfunction "VCC_17") (pintype "passive"))
    )
    (net (code "25") (name "Net-(U3-BOOT)") (class "Default")
      (node (ref "C20") (pin "1") (pinfunction "1_1") (pintype "passive"))
      (node (ref "U3") (pin "6") (pinfunction "BOOT_6") (pintype "passive"))
    )
    (net (code "26") (name "Net-(U3-FB)") (class "Default")
      (node (ref "C23") (pin "1") (pinfunction "1_1") (pintype "passive"))
      (node (ref "R13") (pin "2") (pinfunction "2_2") (pintype "passive"))
      (node (ref "R14") (pin "1") (pinfunction "1_1") (pintype "passive"))
      (node (ref "U3") (pin "4") (pinfunction "FB_4") (pintype "passive"))
    )
    (net (code "27") (name "Net-(U3-SW)") (class "Default")
      (node (ref "C20") (pin "2") (pinfunction "2_2") (pintype "passive"))
      (node (ref "L3") (pin "1") (pinfunction "1_1") (pintype "passive"))
      (node (ref "U3") (pin "2") (pinfunction "SW_2") (pintype "passive"))
    )
    (net (code "28") (name "Net-(U4-PGI)") (class "Default")
      (node (ref "R15") (pin "2") (pinfunction "2_2") (pintype "passive"))
      (node (ref "R16") (pin "1") (pinfunction "1_1") (pintype "passive"))
      (node (ref "U4") (pin "1") (pinfunction "PGI_1") (pintype "passive"))
    )
    (net (code "29") (name "VBUS") (class "Default")
      (node (ref "C21") (pin "2") (pinfunction "2_2") (pintype "passive"))
      (node (ref "C22") (pin "2") (pinfunction "2_2") (pintype "passive"))
      (node (ref "JP2") (pin "6") (pinfunction "6_6") (pintype "passive"))
      (node (ref "JP2") (pin "8") (pinfunction "8_8") (pintype "passive"))
      (node (ref "R15") (pin "1") (pinfunction "1_1") (pintype "passive"))
      (node (ref "U3") (pin "3") (pinfunction "VIN_3") (pintype "passive"))
    )
    (net (code "30") (name "VCC3.3V") (class "Default")
      (node (ref "C26") (pin "1") (pinfunction "1_1") (pintype "passive"))
      (node (ref "C31") (pin "2") (pinfunction "2_2") (pintype "passive"))
      (node (ref "C32") (pin "2") (pinfunction "2_2") (pintype "passive"))
      (node (ref "C33") (pin "2") (pinfunction "2_2") (pintype "passive"))
      (node (ref "C34") (pin "2") (pinfunction "2_2") (pintype "passive"))
      (node (ref "C7") (pin "1") (pinfunction "1_1") (pintype "passive"))
      (node (ref "JP4") (pin "1") (pinfunction "1_1") (pintype "passive"))
      (node (ref "JP4") (pin "13") (pinfunction "13_13") (pintype "passive"))
      (node (ref "JP4") (pin "14") (pinfunction "14_14") (pintype "passive"))
      (node (ref "JP4") (pin "24") (pinfunction "24_24") (pintype "passive"))
      (node (ref "L1") (pin "2") (pinfunction "2_2") (pintype "passive"))
      (node (ref "R1") (pin "1") (pinfunction "1_1") (pintype "passive"))
      (node (ref "U4") (pin "5") (pinfunction "VS33_5") (pintype "passive"))
    )
    (net (code "31") (name "VCC5.0V") (class "Default")
      (node (ref "C1") (pin "1") (pinfunction "1_1") (pintype "passive"))
      (node (ref "C12") (pin "2") (pinfunction "2_2") (pintype "passive"))
      (node (ref "C13") (pin "2") (pinfunction "2_2") (pintype "passive"))
      (node (ref "C14") (pin "2") (pinfunction "2_2") (pintype "passive"))
      (node (ref "C15") (pin "2") (pinfunction "2_2") (pintype "passive"))
      (node (ref "C4") (pin "1") (pinfunction "1_1") (pintype "passive"))
      (node (ref "JP4") (pin "10") (pinfunction "10_10") (pintype "passive"))
      (node (ref "JP4") (pin "11") (pinfunction "11_11") (pintype "passive"))
      (node (ref "JP4") (pin "16") (pinfunction "16_16") (pintype "passive"))
      (node (ref "JP4") (pin "18") (pinfunction "18_18") (pintype "passive"))
      (node (ref "JP4") (pin "9") (pinfunction "9_9") (pintype "passive"))
      (node (ref "L2") (pin "2") (pinfunction "2_2") (pintype "passive"))
      (node (ref "R17") (pin "2") (pinfunction "2_2") (pintype "passive"))
      (node (ref "R7") (pin "1") (pinfunction "1_1") (pintype "passive"))
      (node (ref "U4") (pin "6") (pinfunction "VS5_6") (pintype "passive"))
    )
    (net (code "32") (name "VCC5VSB") (class "Default")
      (node (ref "C19") (pin "1") (pinfunction "1_1") (pintype "passive"))
      (node (ref "C23") (pin "2") (pinfunction "2_2") (pintype "passive"))
      (node (ref "C24") (pin "1") (pinfunction "1_1") (pintype "passive"))
      (node (ref "C25") (pin "1") (pinfunction "1_1") (pintype "passive"))
      (node (ref "D1") (pin "1") (pinfunction "A_1") (pintype "passive"))
      (node (ref "JP4") (pin "21") (pinfunction "21_21") (pintype "passive"))
      (node (ref "L3") (pin "2") (pinfunction "2_2") (pintype "passive"))
      (node (ref "R13") (pin "1") (pinfunction "1_1") (pintype "passive"))
    )
    (net (code "33") (name "VOUT12V") (class "Default")
      (node (ref "C10") (pin "2") (pinfunction "2_2") (pintype "passive"))
      (node (ref "C11") (pin "2") (pinfunction "2_2") (pintype "passive"))
      (node (ref "C2") (pin "1") (pinfunction "1_1") (pintype "passive"))
      (node (ref "C27") (pin "2") (pinfunction "2_2") (pintype "passive"))
      (node (ref "C28") (pin "2") (pinfunction "2_2") (pintype "passive"))
      (node (ref "C29") (pin "2") (pinfunction "2_2") (pintype "passive"))
      (node (ref "C3") (pin "1") (pinfunction "1_1") (pintype "passive"))
      (node (ref "C30") (pin "2") (pinfunction "2_2") (pintype "passive"))
      (node (ref "C5") (pin "2") (pinfunction "2_2") (pintype "passive"))
      (node (ref "C6") (pin "2") (pinfunction "2_2") (pintype "passive"))
      (node (ref "C8") (pin "1") (pinfunction "1_1") (pintype "passive"))
      (node (ref "C9") (pin "1") (pinfunction "1_1") (pintype "passive"))
      (node (ref "D2") (pin "1") (pinfunction "A_1") (pintype "passive"))
      (node (ref "E1") (pin "1") (pinfunction "A_1") (pintype "passive"))
      (node (ref "E2") (pin "1") (pinfunction "A_1") (pintype "passive"))
      (node (ref "E3") (pin "1") (pinfunction "A_1") (pintype "passive"))
      (node (ref "E4") (pin "1") (pinfunction "A_1") (pintype "passive"))
      (node (ref "E5") (pin "1") (pinfunction "A_1") (pintype "passive"))
      (node (ref "E6") (pin "1") (pinfunction "A_1") (pintype "passive"))
      (node (ref "JP1") (pin "10") (pinfunction "10_10") (pintype "passive"))
      (node (ref "JP1") (pin "11") (pinfunction "11_11") (pintype "passive"))
      (node (ref "JP1") (pin "12") (pinfunction "12_12") (pintype "passive"))
      (node (ref "JP1") (pin "13") (pinfunction "13_13") (pintype "passive"))
      (node (ref "JP1") (pin "14") (pinfunction "14_14") (pintype "passive"))
      (node (ref "JP1") (pin "15") (pinfunction "15_15") (pintype "passive"))
      (node (ref "JP1") (pin "16") (pinfunction "16_16") (pintype "passive"))
      (node (ref "JP1") (pin "9") (pinfunction "9_9") (pintype "passive"))
      (node (ref "JP2") (pin "11") (pinfunction "11_11") (pintype "passive"))
      (node (ref "JP2") (pin "13") (pinfunction "13_13") (pintype "passive"))
      (node (ref "JP2") (pin "15") (pinfunction "15_15") (pintype "passive"))
      (node (ref "JP2") (pin "9") (pinfunction "9_9") (pintype "passive"))
      (node (ref "JP3") (pin "10") (pinfunction "10_10") (pintype "passive"))
      (node (ref "JP3") (pin "11") (pinfunction "11_11") (pintype "passive"))
      (node (ref "JP3") (pin "12") (pinfunction "12_12") (pintype "passive"))
      (node (ref "JP3") (pin "13") (pinfunction "13_13") (pintype "passive"))
      (node (ref "JP3") (pin "14") (pinfunction "14_14") (pintype "passive"))
      (node (ref "JP3") (pin "15") (pinfunction "15_15") (pintype "passive"))
      (node (ref "JP3") (pin "16") (pinfunction "16_16") (pintype "passive"))
      (node (ref "JP3") (pin "9") (pinfunction "9_9") (pintype "passive"))
      (node (ref "JP4") (pin "22") (pinfunction "22_22") (pintype "passive"))
      (node (ref "JP4") (pin "23") (pinfunction "23_23") (pintype "passive"))
      (node (ref "JP5") (pin "1") (pinfunction "1_1") (pintype "passive"))
      (node (ref "JP5") (pin "2") (pinfunction "2_2") (pintype "passive"))
      (node (ref "JP5") (pin "3") (pinfunction "3_3") (pintype "passive"))
      (node (ref "JP5") (pin "4") (pinfunction "4_4") (pintype "passive"))
      (node (ref "JP5") (pin "5") (pinfunction "5_5") (pintype "passive"))
      (node (ref "JP5") (pin "6") (pinfunction "6_6") (pintype "passive"))
      (node (ref "R18") (pin "1") (pinfunction "1_1") (pintype "passive"))
      (node (ref "R18") (pin "2") (pinfunction "2_2") (pintype "passive"))
      (node (ref "R19") (pin "1") (pinfunction "1_1") (pintype "passive"))
      (node (ref "R19") (pin "2") (pinfunction "2_2") (pintype "passive"))
      (node (ref "R2") (pin "2") (pinfunction "2_2") (pintype "passive"))
      (node (ref "R8") (pin "2") (pinfunction "2_2") (pintype "passive"))
      (node (ref "U1") (pin "2") (pinfunction "VIN_2") (pintype "passive"))
      (node (ref "U1") (pin "3") (pinfunction "VIN_3") (pintype "passive"))
      (node (ref "U1") (pin "4") (pinfunction "VIN_4") (pintype "passive"))
      (node (ref "U1") (pin "5") (pinfunction "VIN_5") (pintype "passive"))
      (node (ref "U2") (pin "2") (pinfunction "VIN_2") (pintype "passive"))
      (node (ref "U2") (pin "3") (pinfunction "VIN_3") (pintype "passive"))
      (node (ref "U2") (pin "4") (pinfunction "VIN_4") (pintype "passive"))
      (node (ref "U2") (pin "5") (pinfunction "VIN_5") (pintype "passive"))
    )
    (net (code "34") (name "unconnected-(JP4-Pad2)") (class "Default")
      (node (ref "JP4") (pin "2") (pinfunction "2_2") (pintype "passive+no_connect"))
    )
    (net (code "35") (name "unconnected-(JP4-Pad8)") (class "Default")
      (node (ref "JP4") (pin "8") (pinfunction "8_8") (pintype "passive+no_connect"))
    )
    (net (code "36") (name "unconnected-(U1-PGOOD-Pad9)") (class "Default")
      (node (ref "U1") (pin "9") (pinfunction "PGOOD_9") (pintype "passive+no_connect"))
    )
    (net (code "37") (name "unconnected-(U2-PGOOD-Pad9)") (class "Default")
      (node (ref "U2") (pin "9") (pinfunction "PGOOD_9") (pintype "passive+no_connect"))
    )
    (net (code "38") (name "unconnected-(U3-EN-Pad5)") (class "Default")
      (node (ref "U3") (pin "5") (pinfunction "EN_5") (pintype "passive+no_connect"))
    )
  )
)
